# Main.net
KiCad netlist of a schematic drawn in Altium Designer
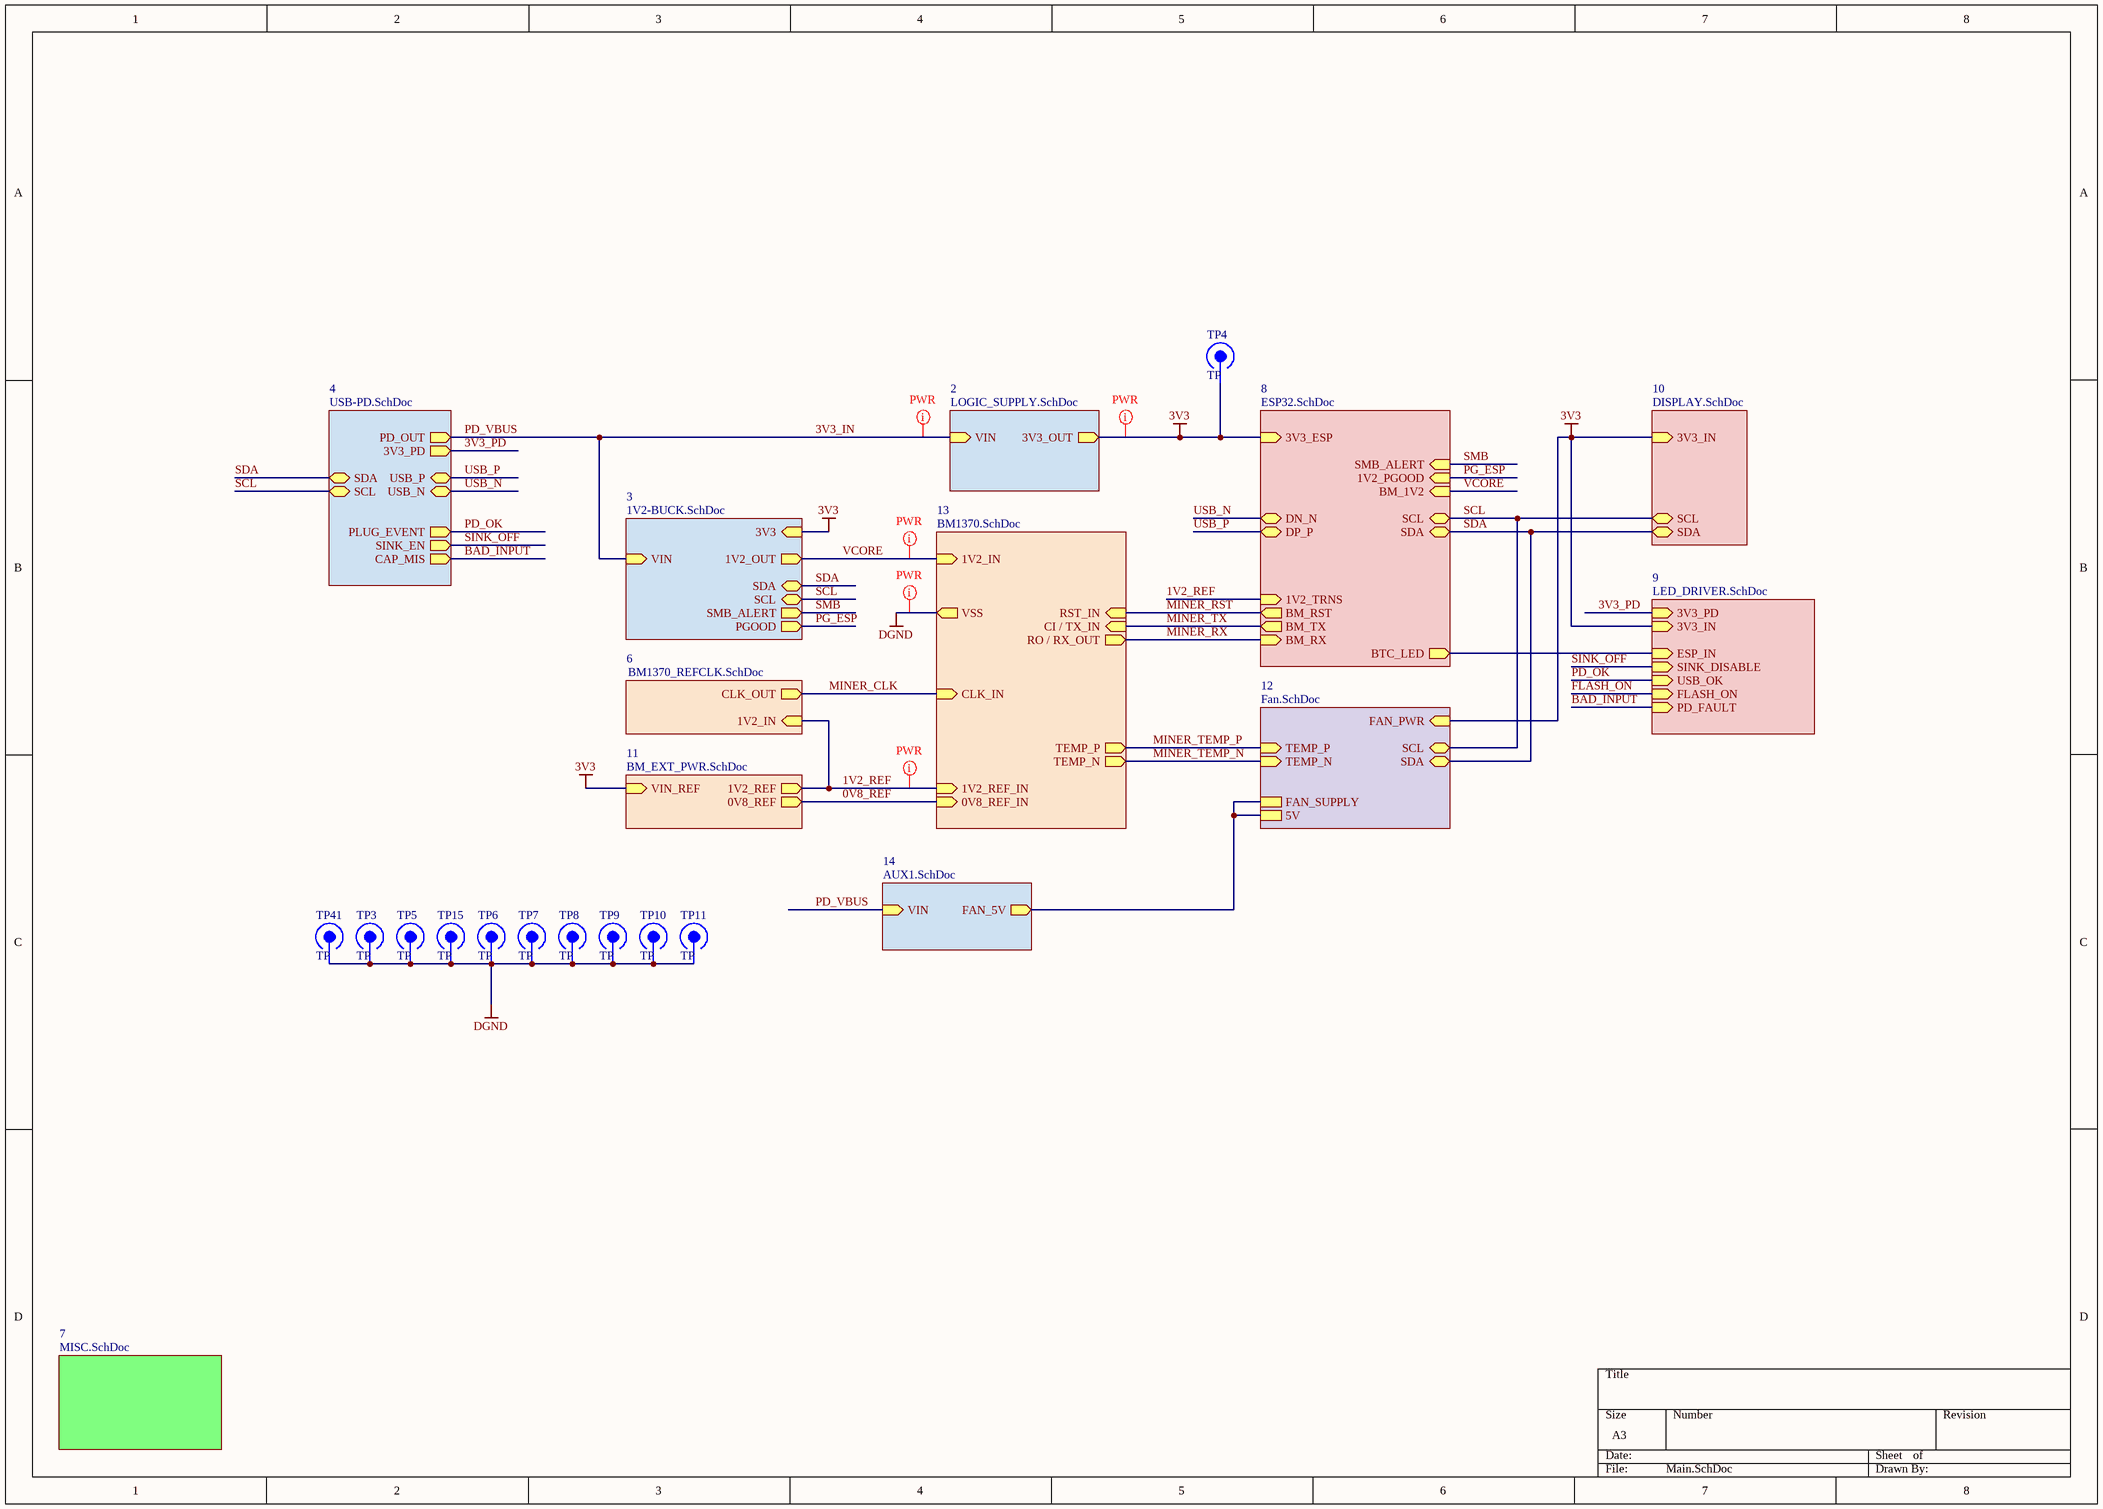
[diagram p0: Main.SchDoc]

(export (version "E")
  (design (tool "Eeschema 10.0.6"))
  (components
    (comp (ref "TP3")
      (value "TP")
      (footprint "TP-Footprint-1")
      (description "digital shovel test point")
      (libsource (lib "Digital Shovel") (part "TP-Symbol-1"))
    )
    (comp (ref "TP4")
      (value "TP")
      (footprint "TP-Footprint-1")
      (description "digital shovel test point")
      (libsource (lib "Digital Shovel") (part "TP-Symbol-1"))
    )
    (comp (ref "TP5")
      (value "TP")
      (footprint "TP-Footprint-1")
      (description "digital shovel test point")
      (libsource (lib "Digital Shovel") (part "TP-Symbol-1"))
    )
    (comp (ref "TP6")
      (value "TP")
      (footprint "TP-Footprint-1")
      (description "digital shovel test point")
      (libsource (lib "Digital Shovel") (part "TP-Symbol-1"))
    )
    (comp (ref "TP7")
      (value "TP")
      (footprint "TP-Footprint-1")
      (description "digital shovel test point")
      (libsource (lib "Digital Shovel") (part "TP-Symbol-1"))
    )
    (comp (ref "TP8")
      (value "TP")
      (footprint "TP-Footprint-1")
      (description "digital shovel test point")
      (libsource (lib "Digital Shovel") (part "TP-Symbol-1"))
    )
    (comp (ref "TP9")
      (value "TP")
      (footprint "TP-Footprint-1")
      (description "digital shovel test point")
      (libsource (lib "Digital Shovel") (part "TP-Symbol-1"))
    )
    (comp (ref "TP10")
      (value "TP")
      (footprint "TP-Footprint-1")
      (description "digital shovel test point")
      (libsource (lib "Digital Shovel") (part "TP-Symbol-1"))
    )
    (comp (ref "TP11")
      (value "TP")
      (footprint "TP-Footprint-1")
      (description "digital shovel test point")
      (libsource (lib "Digital Shovel") (part "TP-Symbol-1"))
    )
    (comp (ref "TP15")
      (value "TP")
      (footprint "TP-Footprint-1")
      (description "digital shovel test point")
      (libsource (lib "Digital Shovel") (part "TP-Symbol-1"))
    )
    (comp (ref "TP41")
      (value "TP")
      (footprint "TP-Footprint-1")
      (description "digital shovel test point")
      (libsource (lib "Digital Shovel") (part "TP-Symbol-1"))
    )
  )
  (nets
    (net (code "24") (name "3V3") (class "Default") (node (ref "TP4") (pin "1") (pintype "passive")))
    (net (code "25") (name "DGND") (class "Default")
      (node (ref "TP10") (pin "1") (pintype "passive"))
      (node (ref "TP11") (pin "1") (pintype "passive"))
      (node (ref "TP15") (pin "1") (pintype "passive"))
      (node (ref "TP3") (pin "1") (pintype "passive"))
      (node (ref "TP41") (pin "1") (pintype "passive"))
      (node (ref "TP5") (pin "1") (pintype "passive"))
      (node (ref "TP6") (pin "1") (pintype "passive"))
      (node (ref "TP7") (pin "1") (pintype "passive"))
      (node (ref "TP8") (pin "1") (pintype "passive"))
      (node (ref "TP9") (pin "1") (pintype "passive"))
    )
  )
)
